# MiniAB-Board.net
KiCad netlist of a schematic drawn in Altium Designer
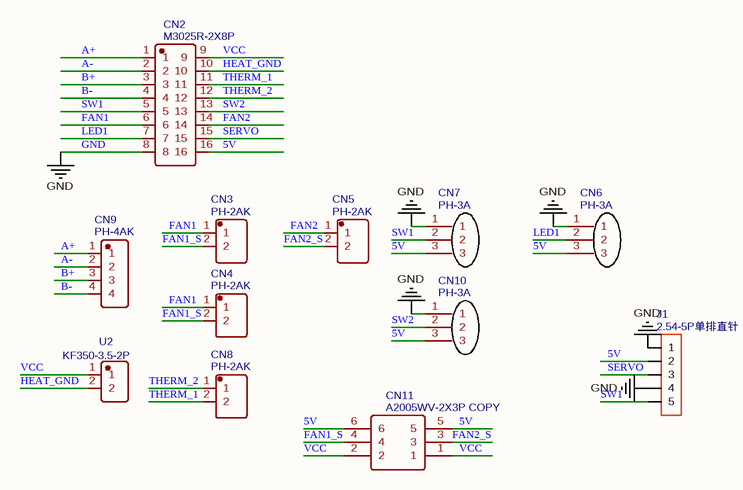
[diagram p0: MiniAB-Board.schdoc]

(export (version "E")
  (design (tool "Eeschema 10.0.6"))
  (components
    (comp (ref "CN2")
      (value "M3025R-2X8P")
      (footprint "CONN-TH_M3025R-2X8P")
      (fields
        (field (name "BOM_SUPPLIER PART") "C501326")
        (field (name "BOM_MANUFACTURER PART") "M3025R-2x8P")
        (field (name "CONTRIBUTOR") "LCSC")
      )
      (libsource (lib "altium-import") (part "root_0_M3025R-2X8P_"))
    )
    (comp (ref "CN3")
      (value "PH-2AK")
      (footprint "CONN-TH_PH-2A")
      (fields (field (name "BOM_SUPPLIER PART") "C8886"))
      (libsource (lib "altium-import") (part "root_0_PH-2AK_"))
    )
    (comp (ref "CN4")
      (value "PH-2AK")
      (footprint "CONN-TH_PH-2A")
      (fields (field (name "BOM_SUPPLIER PART") "C8886"))
      (libsource (lib "altium-import") (part "root_0_PH-2AK_"))
    )
    (comp (ref "CN5")
      (value "PH-2AK")
      (footprint "CONN-TH_PH-2A")
      (fields (field (name "BOM_SUPPLIER PART") "C8886"))
      (libsource (lib "altium-import") (part "root_0_PH-2AK_"))
    )
    (comp (ref "CN6")
      (value "PH-3A")
      (footprint "CONN-TH_3P-P2.00_PH-3AK")
      (fields (field (name "BOM_SUPPLIER PART") "C146083") (field (name "CONTRIBUTOR") "LCSC"))
      (libsource (lib "altium-import") (part "root_3_PH-3A_"))
    )
    (comp (ref "CN7")
      (value "PH-3A")
      (footprint "CONN-TH_3P-P2.00_PH-3AK")
      (fields (field (name "BOM_SUPPLIER PART") "C146083") (field (name "CONTRIBUTOR") "LCSC"))
      (libsource (lib "altium-import") (part "root_3_PH-3A_"))
    )
    (comp (ref "CN8")
      (value "PH-2AK")
      (footprint "CONN-TH_PH-2A")
      (fields (field (name "BOM_SUPPLIER PART") "C8886"))
      (libsource (lib "altium-import") (part "root_0_PH-2AK_"))
    )
    (comp (ref "CN9")
      (value "PH-4AK")
      (footprint "CONN-TH_PH-4AK")
      (fields (field (name "BOM_SUPPLIER PART") "C722776") (field (name "CONTRIBUTOR") "LCSC"))
      (libsource (lib "altium-import") (part "root_0_PH-4AK_"))
    )
    (comp (ref "CN10")
      (value "PH-3A")
      (footprint "CONN-TH_3P-P2.00_PH-3AK")
      (fields (field (name "BOM_SUPPLIER PART") "C146083") (field (name "CONTRIBUTOR") "LCSC"))
      (libsource (lib "altium-import") (part "root_3_PH-3A_"))
    )
    (comp (ref "CN11")
      (value "A2005WV-2X3P COPY")
      (footprint "HDR-TH_6P-P2.00-V-M-R2-C3-S2.00")
      (fields
        (field (name "BOM_SUPPLIER PART") "C225288")
        (field (name "BOM_MANUFACTURER PART") "A2005WV-2x3P")
        (field (name "CONTRIBUTOR") "LCSC")
      )
      (libsource (lib "altium-import") (part "root_1_A2005WV-2X3P COPY_"))
    )
    (comp (ref "J1")
      (value "2.54-5P单排直针")
      (footprint "2.54-5P直针")
      (fields (field (name "CONTRIBUTOR") "xf18898418890"))
      (libsource (lib "altium-import") (part "root_0_2.54-5P单排直针_"))
    )
    (comp (ref "U2")
      (value "KF350-3.5-2P")
      (footprint "CONN-TH_P3.50_KF350-3.5-2P")
      (fields (field (name "BOM_SUPPLIER PART") "C474892") (field (name "CONTRIBUTOR") "LCSC"))
      (libsource (lib "altium-import") (part "root_0_KF350-3.5-2P_"))
    )
  )
  (nets
    (net (code "1") (name "/5V") (class "Default")
      (node (ref "CN10") (pin "3") (pinfunction "3_3") (pintype "passive"))
      (node (ref "CN11") (pin "5") (pinfunction "5_5") (pintype "passive"))
      (node (ref "CN11") (pin "6") (pinfunction "6_6") (pintype "passive"))
      (node (ref "CN2") (pin "16") (pinfunction "16_16") (pintype "passive"))
      (node (ref "CN6") (pin "3") (pinfunction "3_3") (pintype "passive"))
      (node (ref "CN7") (pin "3") (pinfunction "3_3") (pintype "passive"))
      (node (ref "J1") (pin "2") (pinfunction "2_2") (pintype "passive"))
    )
    (net (code "2") (name "/A+") (class "Default")
      (node (ref "CN2") (pin "1") (pinfunction "1_1") (pintype "passive"))
      (node (ref "CN9") (pin "1") (pinfunction "1_1") (pintype "passive"))
    )
    (net (code "3") (name "/A-") (class "Default")
      (node (ref "CN2") (pin "2") (pinfunction "2_2") (pintype "passive"))
      (node (ref "CN9") (pin "2") (pinfunction "2_2") (pintype "passive"))
    )
    (net (code "4") (name "/B+") (class "Default")
      (node (ref "CN2") (pin "3") (pinfunction "3_3") (pintype "passive"))
      (node (ref "CN9") (pin "3") (pinfunction "3_3") (pintype "passive"))
    )
    (net (code "5") (name "/B-") (class "Default")
      (node (ref "CN2") (pin "4") (pinfunction "4_4") (pintype "passive"))
      (node (ref "CN9") (pin "4") (pinfunction "4_4") (pintype "passive"))
    )
    (net (code "6") (name "/FAN1") (class "Default")
      (node (ref "CN2") (pin "6") (pinfunction "6_6") (pintype "passive"))
      (node (ref "CN3") (pin "1") (pinfunction "1_1") (pintype "passive"))
      (node (ref "CN4") (pin "1") (pinfunction "1_1") (pintype "passive"))
    )
    (net (code "7") (name "/FAN1_S") (class "Default")
      (node (ref "CN11") (pin "4") (pinfunction "4_4") (pintype "passive"))
      (node (ref "CN3") (pin "2") (pinfunction "2_2") (pintype "passive"))
      (node (ref "CN4") (pin "2") (pinfunction "2_2") (pintype "passive"))
    )
    (net (code "8") (name "/FAN2") (class "Default")
      (node (ref "CN2") (pin "14") (pinfunction "14_14") (pintype "passive"))
      (node (ref "CN5") (pin "1") (pinfunction "1_1") (pintype "passive"))
    )
    (net (code "9") (name "/FAN2_S") (class "Default")
      (node (ref "CN11") (pin "3") (pinfunction "3_3") (pintype "passive"))
      (node (ref "CN5") (pin "2") (pinfunction "2_2") (pintype "passive"))
    )
    (net (code "10") (name "/HEAT_GND") (class "Default")
      (node (ref "CN2") (pin "10") (pinfunction "10_10") (pintype "passive"))
      (node (ref "U2") (pin "2") (pinfunction "2_2") (pintype "passive"))
    )
    (net (code "11") (name "/LED1") (class "Default")
      (node (ref "CN2") (pin "7") (pinfunction "7_7") (pintype "passive"))
      (node (ref "CN6") (pin "2") (pinfunction "2_2") (pintype "passive"))
    )
    (net (code "12") (name "/SERVO") (class "Default")
      (node (ref "CN2") (pin "15") (pinfunction "15_15") (pintype "passive"))
      (node (ref "J1") (pin "3") (pinfunction "3_3") (pintype "passive"))
    )
    (net (code "13") (name "/SW1") (class "Default")
      (node (ref "CN2") (pin "5") (pinfunction "5_5") (pintype "passive"))
      (node (ref "CN7") (pin "2") (pinfunction "2_2") (pintype "passive"))
      (node (ref "J1") (pin "5") (pinfunction "5_5") (pintype "passive"))
    )
    (net (code "14") (name "/SW2") (class "Default")
      (node (ref "CN10") (pin "2") (pinfunction "2_2") (pintype "passive"))
      (node (ref "CN2") (pin "13") (pinfunction "13_13") (pintype "passive"))
    )
    (net (code "15") (name "/THERM_1") (class "Default")
      (node (ref "CN2") (pin "11") (pinfunction "11_11") (pintype "passive"))
      (node (ref "CN8") (pin "2") (pinfunction "2_2") (pintype "passive"))
    )
    (net (code "16") (name "/THERM_2") (class "Default")
      (node (ref "CN2") (pin "12") (pinfunction "12_12") (pintype "passive"))
      (node (ref "CN8") (pin "1") (pinfunction "1_1") (pintype "passive"))
    )
    (net (code "17") (name "/VCC") (class "Default")
      (node (ref "CN11") (pin "1") (pinfunction "1_1") (pintype "passive"))
      (node (ref "CN11") (pin "2") (pinfunction "2_2") (pintype "passive"))
      (node (ref "CN2") (pin "9") (pinfunction "9_9") (pintype "passive"))
      (node (ref "U2") (pin "1") (pinfunction "1_1") (pintype "passive"))
    )
    (net (code "18") (name "GND") (class "Default")
      (node (ref "CN10") (pin "1") (pinfunction "1_1") (pintype "passive"))
      (node (ref "CN2") (pin "8") (pinfunction "8_8") (pintype "passive"))
      (node (ref "CN6") (pin "1") (pinfunction "1_1") (pintype "passive"))
      (node (ref "CN7") (pin "1") (pinfunction "1_1") (pintype "passive"))
      (node (ref "J1") (pin "1") (pinfunction "1_1") (pintype "passive"))
      (node (ref "J1") (pin "4") (pinfunction "4_4") (pintype "passive"))
    )
  )
)
